# Peripheral.net
KiCad netlist of a schematic drawn in Altium Designer
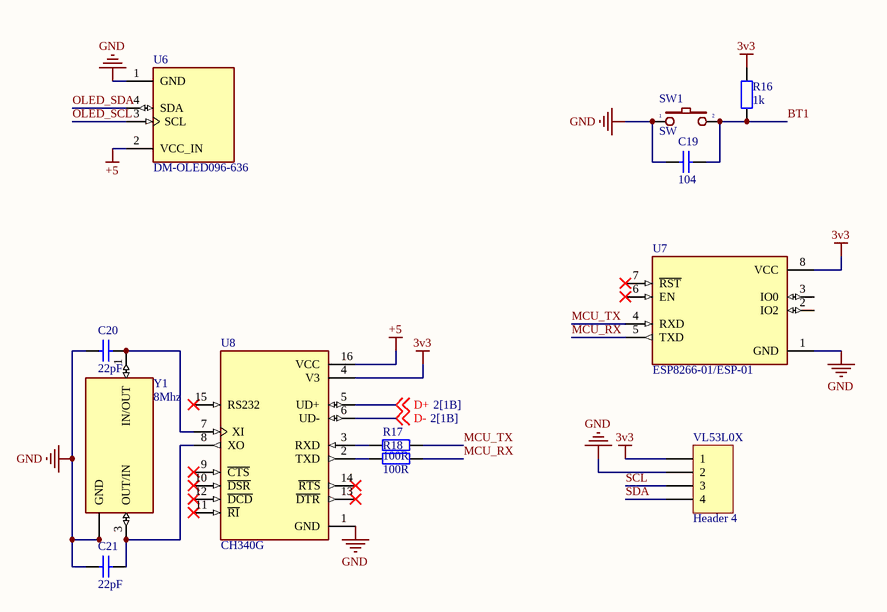
[diagram p0: Peripheral.SchDoc]

(export (version "E")
  (design (tool "Eeschema 10.0.6"))
  (components
    (comp (ref "C19")
      (value "104")
      (footprint "C-NP-0805")
      (description "Non-polarized Capacitor")
      (fields (field (name "Comment") "Cap Non-pol") (field (name "PUBLISHER") "Altium Limited"))
      (libsource (lib "Kiet") (part "Cap Non-pol"))
    )
    (comp (ref "C20")
      (value "22pF")
      (footprint "C-NP-0805")
      (description "Non-polarized Capacitor")
      (fields (field (name "Comment") "Cap Non-pol") (field (name "PUBLISHER") "Altium Limited"))
      (libsource (lib "Kiet") (part "Cap Non-pol"))
    )
    (comp (ref "C21")
      (value "22pF")
      (footprint "C-NP-0805")
      (description "Non-polarized Capacitor")
      (fields (field (name "Comment") "Cap Non-pol") (field (name "PUBLISHER") "Altium Limited"))
      (libsource (lib "Kiet") (part "Cap Non-pol"))
    )
    (comp (ref "R16")
      (value "1k")
      (footprint "DIEN TRO 0805")
      (description "RES_0805")
      (fields (field (name "Comment") "RES_SMD_0805") (field (name "PUBLISHER") "Altium Limited"))
      (libsource (lib "") (part "RES_SMD_0805_1"))
    )
    (comp (ref "R17")
      (value "100R")
      (footprint "DIEN TRO 0805")
      (description "RES_0805")
      (fields (field (name "Comment") "RES_SMD_0805") (field (name "PUBLISHER") "Altium Limited"))
      (libsource (lib "Kiet") (part "RES_SMD_0805"))
    )
    (comp (ref "R18")
      (value "100R")
      (footprint "DIEN TRO 0805")
      (description "RES_0805")
      (fields (field (name "Comment") "RES_SMD_0805") (field (name "PUBLISHER") "Altium Limited"))
      (libsource (lib "Kiet") (part "RES_SMD_0805"))
    )
    (comp (ref "SW1")
      (value "SW")
      (footprint "SW2")
      (description "Switch button 2 pin")
      (libsource (lib "Kiet") (part "SW2"))
    )
    (comp (ref "U6")
      (value "DM-OLED096-636")
      (footprint "MODULE_DM-OLED096-636")
      (description "0.96â€ 128 X 64 MONOCHROME GRAPHIC OLED DISPLAY MODULE - I2C")
      (fields (field (name "MF") "Display Module"))
      (libsource (lib "DM-OLED096-636") (part "DM-OLED096-636"))
    )
    (comp (ref "U7")
      (value "ESP8266-01/ESP-01")
      (footprint "XCVR_ESP8266-01/ESP-01")
      (libsource (lib "ESP8266-01_ESP-01") (part "ESP8266-01/ESP-01"))
    )
    (comp (ref "U8")
      (value "CH340G")
      (footprint "SOIC127P600X180-16N")
      (description "USB Interface Integrated Circuit")
      (fields (field (name "MP") "Ch340G") (field (name "MF") "WCH"))
      (libsource (lib "CH340G") (part "CH340G"))
    )
    (comp (ref "VL53L0X")
      (value "Header 4")
      (footprint "Header 4")
      (description "Header, 4-Pin")
      (fields (field (name "PUBLISHER") "Altium Limited"))
      (libsource (lib "Kiet") (part "Header 4"))
    )
    (comp (ref "Y1")
      (value "8Mhz")
      (footprint "XTAL_ECS-250-6-33B2-CTN-TR3")
      (fields (field (name "MP") "ECS-250-6-33B2-CTN-TR3"))
      (libsource (lib "ECS-250-6-33B2-CTN-TR3") (part "ECS-250-6-33B2-CTN-TR3"))
    )
  )
  (nets
    (net (code "1") (name "+5") (class "Default")
      (node (ref "U6") (pin "2") (pinfunction "VCC_IN_2") (pintype "power_in"))
      (node (ref "U8") (pin "16") (pinfunction "VCC_16") (pintype "power_in"))
    )
    (net (code "2") (name "/BT1") (class "Default")
      (node (ref "C19") (pin "1") (pinfunction "1_1") (pintype "passive"))
      (node (ref "R16") (pin "1") (pinfunction "1_1") (pintype "passive"))
      (node (ref "SW1") (pin "2") (pinfunction "2_2") (pintype "passive"))
    )
    (net (code "3") (name "/MCU_RX") (class "Default")
      (node (ref "R18") (pin "2") (pinfunction "2_2") (pintype "passive"))
      (node (ref "U7") (pin "5") (pinfunction "TXD_5") (pintype "output"))
    )
    (net (code "4") (name "/MCU_TX") (class "Default")
      (node (ref "R17") (pin "2") (pinfunction "2_2") (pintype "passive"))
      (node (ref "U7") (pin "4") (pinfunction "RXD_4") (pintype "input"))
    )
    (net (code "5") (name "/OLED_SCL") (class "Default")
      (node (ref "U6") (pin "3") (pinfunction "SCL_3") (pintype "input"))
    )
    (net (code "6") (name "/OLED_SDA") (class "Default")
      (node (ref "U6") (pin "4") (pinfunction "SDA_4") (pintype "bidirectional"))
    )
    (net (code "7") (name "/SCL") (class "Default")
      (node (ref "VL53L0X") (pin "3") (pinfunction "3_3") (pintype "passive"))
    )
    (net (code "8") (name "/SDA") (class "Default")
      (node (ref "VL53L0X") (pin "4") (pinfunction "4_4") (pintype "passive"))
    )
    (net (code "9") (name "3v3") (class "Default")
      (node (ref "R16") (pin "2") (pinfunction "2_2") (pintype "passive"))
      (node (ref "U7") (pin "8") (pinfunction "VCC_8") (pintype "power_in"))
      (node (ref "U8") (pin "4") (pinfunction "V3_4") (pintype "power_in"))
      (node (ref "VL53L0X") (pin "1") (pinfunction "1_1") (pintype "passive"))
    )
    (net (code "10") (name "D+") (class "Default")
      (node (ref "U8") (pin "5") (pinfunction "UD+_5") (pintype "bidirectional"))
    )
    (net (code "11") (name "D-") (class "Default")
      (node (ref "U8") (pin "6") (pinfunction "UD-_6") (pintype "bidirectional"))
    )
    (net (code "12") (name "GND") (class "Default")
      (node (ref "C19") (pin "2") (pinfunction "2_2") (pintype "passive"))
      (node (ref "C20") (pin "2") (pinfunction "2_2") (pintype "passive"))
      (node (ref "C21") (pin "2") (pinfunction "2_2") (pintype "passive"))
      (node (ref "SW1") (pin "1") (pinfunction "1_1") (pintype "passive"))
      (node (ref "U6") (pin "1") (pinfunction "GND_1") (pintype "power_in"))
      (node (ref "U7") (pin "1") (pinfunction "GND_1") (pintype "power_in"))
      (node (ref "U8") (pin "1") (pinfunction "GND_1") (pintype "power_in"))
      (node (ref "VL53L0X") (pin "2") (pinfunction "2_2") (pintype "passive"))
      (node (ref "Y1") (pin "2") (pinfunction "GND_2") (pintype "power_in"))
      (node (ref "Y1") (pin "4") (pinfunction "GND_4") (pintype "power_in"))
    )
    (net (code "13") (name "Net-(U8-RXD)") (class "Default")
      (node (ref "R17") (pin "1") (pinfunction "1_1") (pintype "passive"))
      (node (ref "U8") (pin "3") (pinfunction "RXD_3") (pintype "input"))
    )
    (net (code "14") (name "Net-(U8-TXD)") (class "Default")
      (node (ref "R18") (pin "1") (pinfunction "1_1") (pintype "passive"))
      (node (ref "U8") (pin "2") (pinfunction "TXD_2") (pintype "output"))
    )
    (net (code "15") (name "Net-(U8-XI)") (class "Default")
      (node (ref "C20") (pin "1") (pinfunction "1_1") (pintype "passive"))
      (node (ref "U8") (pin "7") (pinfunction "XI_7") (pintype "input"))
      (node (ref "Y1") (pin "1") (pinfunction "IN/OUT_1") (pintype "bidirectional"))
    )
    (net (code "16") (name "Net-(U8-XO)") (class "Default")
      (node (ref "C21") (pin "1") (pinfunction "1_1") (pintype "passive"))
      (node (ref "U8") (pin "8") (pinfunction "XO_8") (pintype "output"))
      (node (ref "Y1") (pin "3") (pinfunction "OUT/IN_3") (pintype "bidirectional"))
    )
    (net (code "17") (name "unconnected-(U7-EN-Pad6)") (class "Default")
      (node (ref "U7") (pin "6") (pinfunction "EN_6") (pintype "input+no_connect"))
    )
    (net (code "18") (name "unconnected-(U7-IO0-Pad3)") (class "Default")
      (node (ref "U7") (pin "3") (pinfunction "IO0_3") (pintype "bidirectional"))
    )
    (net (code "19") (name "unconnected-(U7-IO2-Pad2)") (class "Default")
      (node (ref "U7") (pin "2") (pinfunction "IO2_2") (pintype "bidirectional"))
    )
    (net (code "20") (name "unconnected-(U7-~{RST}-Pad7)") (class "Default")
      (node (ref "U7") (pin "7") (pinfunction "~{RST}_7") (pintype "input+no_connect"))
    )
    (net (code "21") (name "unconnected-(U8-RS232-Pad15)") (class "Default")
      (node (ref "U8") (pin "15") (pinfunction "RS232_15") (pintype "input+no_connect"))
    )
    (net (code "22") (name "unconnected-(U8-~{CTS}-Pad9)") (class "Default")
      (node (ref "U8") (pin "9") (pinfunction "~{CTS}_9") (pintype "input+no_connect"))
    )
    (net (code "23") (name "unconnected-(U8-~{DCD}-Pad12)") (class "Default")
      (node (ref "U8") (pin "12") (pinfunction "~{DCD}_12") (pintype "input+no_connect"))
    )
    (net (code "24") (name "unconnected-(U8-~{DSR}-Pad10)") (class "Default")
      (node (ref "U8") (pin "10") (pinfunction "~{DSR}_10") (pintype "input+no_connect"))
    )
    (net (code "25") (name "unconnected-(U8-~{DTR}-Pad13)") (class "Default")
      (node (ref "U8") (pin "13") (pinfunction "~{DTR}_13") (pintype "output+no_connect"))
    )
    (net (code "26") (name "unconnected-(U8-~{RI}-Pad11)") (class "Default")
      (node (ref "U8") (pin "11") (pinfunction "~{RI}_11") (pintype "input+no_connect"))
    )
    (net (code "27") (name "unconnected-(U8-~{RTS}-Pad14)") (class "Default")
      (node (ref "U8") (pin "14") (pinfunction "~{RTS}_14") (pintype "output+no_connect"))
    )
  )
)
